# cnc-diff-line-driver.net
KiCad netlist of a schematic drawn in EAGLE
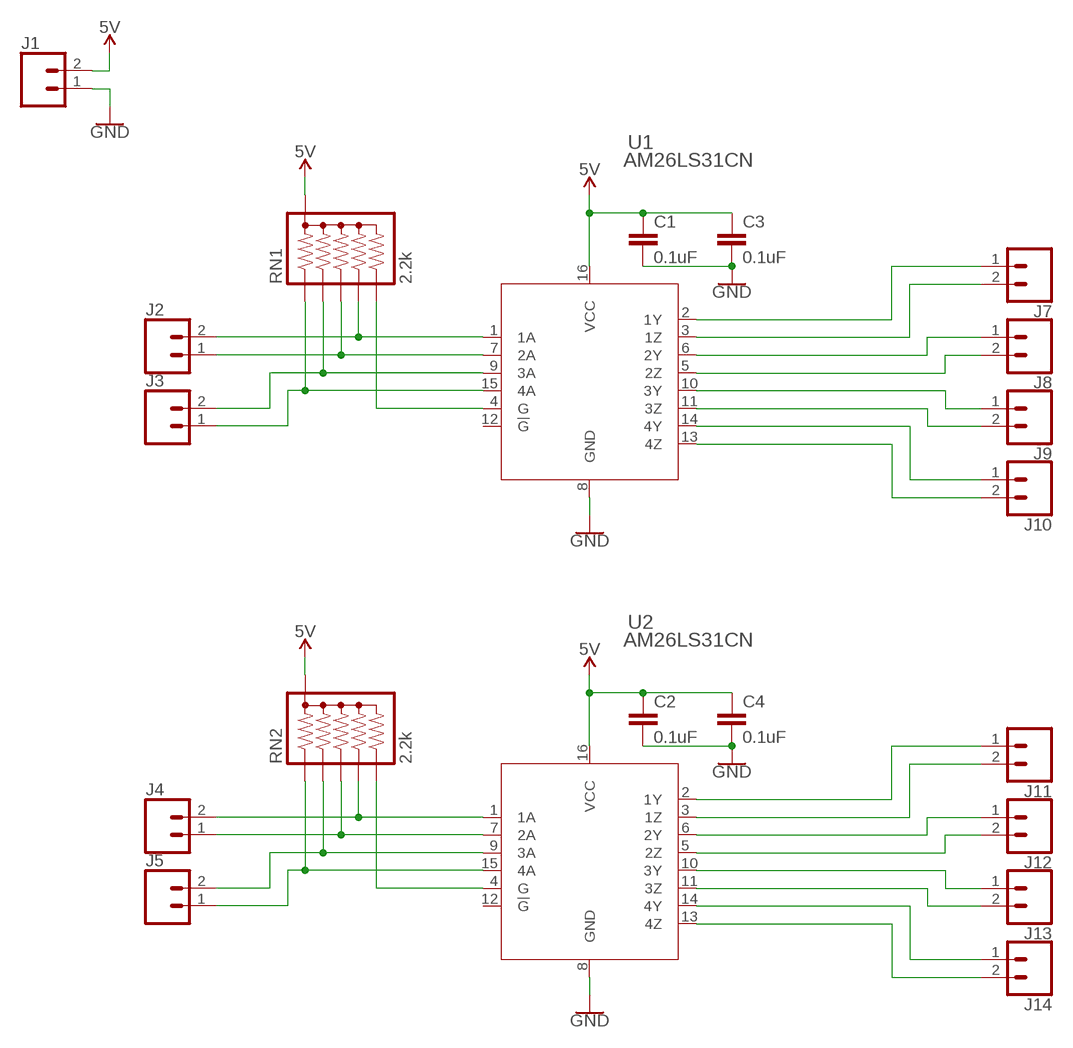
[diagram p0: schematic, sheet 1]

(export (version "E")
  (design (tool "Eeschema 10.0.6"))
  (components
    (comp (ref "C1")
      (value "0.1uF")
      (footprint "eagle-import:CAP-PTH-SMALL-KIT")
      (libsource (lib "eagle-import") (part "0.1UF-KIT-EZ-50V-20%"))
    )
    (comp (ref "C2")
      (value "0.1uF")
      (footprint "eagle-import:CAP-PTH-SMALL-KIT")
      (libsource (lib "eagle-import") (part "0.1UF-KIT-EZ-50V-20%"))
    )
    (comp (ref "C3")
      (value "0.1uF")
      (footprint "eagle-import:CAP-PTH-SMALL-KIT")
      (libsource (lib "eagle-import") (part "0.1UF-KIT-EZ-50V-20%"))
    )
    (comp (ref "C4")
      (value "0.1uF")
      (footprint "eagle-import:CAP-PTH-SMALL-KIT")
      (libsource (lib "eagle-import") (part "0.1UF-KIT-EZ-50V-20%"))
    )
    (comp (ref "J1")
      (value "PHOENIX_CON_5.08MM_SCREW_1888687")
      (footprint "eagle-import:SCREWTERMINAL-5MM-2")
      (libsource (lib "eagle-import") (part "PHOENIX_CON_5.08MM_SCREW_1888687"))
    )
    (comp (ref "J2")
      (value "PHOENIX_CON_5.08MM_SCREW_1888687")
      (footprint "eagle-import:SCREWTERMINAL-5MM-2")
      (libsource (lib "eagle-import") (part "PHOENIX_CON_5.08MM_SCREW_1888687"))
    )
    (comp (ref "J3")
      (value "PHOENIX_CON_5.08MM_SCREW_1888687")
      (footprint "eagle-import:SCREWTERMINAL-5MM-2")
      (libsource (lib "eagle-import") (part "PHOENIX_CON_5.08MM_SCREW_1888687"))
    )
    (comp (ref "J4")
      (value "PHOENIX_CON_5.08MM_SCREW_1888687")
      (footprint "eagle-import:SCREWTERMINAL-5MM-2")
      (libsource (lib "eagle-import") (part "PHOENIX_CON_5.08MM_SCREW_1888687"))
    )
    (comp (ref "J5")
      (value "PHOENIX_CON_5.08MM_SCREW_1888687")
      (footprint "eagle-import:SCREWTERMINAL-5MM-2")
      (libsource (lib "eagle-import") (part "PHOENIX_CON_5.08MM_SCREW_1888687"))
    )
    (comp (ref "J7")
      (value "PHOENIX_CON_5.08MM_SCREW_1888687")
      (footprint "eagle-import:SCREWTERMINAL-5MM-2")
      (libsource (lib "eagle-import") (part "PHOENIX_CON_5.08MM_SCREW_1888687"))
    )
    (comp (ref "J8")
      (value "PHOENIX_CON_5.08MM_SCREW_1888687")
      (footprint "eagle-import:SCREWTERMINAL-5MM-2")
      (libsource (lib "eagle-import") (part "PHOENIX_CON_5.08MM_SCREW_1888687"))
    )
    (comp (ref "J9")
      (value "PHOENIX_CON_5.08MM_SCREW_1888687")
      (footprint "eagle-import:SCREWTERMINAL-5MM-2")
      (libsource (lib "eagle-import") (part "PHOENIX_CON_5.08MM_SCREW_1888687"))
    )
    (comp (ref "J10")
      (value "PHOENIX_CON_5.08MM_SCREW_1888687")
      (footprint "eagle-import:SCREWTERMINAL-5MM-2")
      (libsource (lib "eagle-import") (part "PHOENIX_CON_5.08MM_SCREW_1888687"))
    )
    (comp (ref "J11")
      (value "PHOENIX_CON_5.08MM_SCREW_1888687")
      (footprint "eagle-import:SCREWTERMINAL-5MM-2")
      (libsource (lib "eagle-import") (part "PHOENIX_CON_5.08MM_SCREW_1888687"))
    )
    (comp (ref "J12")
      (value "PHOENIX_CON_5.08MM_SCREW_1888687")
      (footprint "eagle-import:SCREWTERMINAL-5MM-2")
      (libsource (lib "eagle-import") (part "PHOENIX_CON_5.08MM_SCREW_1888687"))
    )
    (comp (ref "J13")
      (value "PHOENIX_CON_5.08MM_SCREW_1888687")
      (footprint "eagle-import:SCREWTERMINAL-5MM-2")
      (libsource (lib "eagle-import") (part "PHOENIX_CON_5.08MM_SCREW_1888687"))
    )
    (comp (ref "J14")
      (value "PHOENIX_CON_5.08MM_SCREW_1888687")
      (footprint "eagle-import:SCREWTERMINAL-5MM-2")
      (libsource (lib "eagle-import") (part "PHOENIX_CON_5.08MM_SCREW_1888687"))
    )
    (comp (ref "RN1")
      (value "2.2k")
      (footprint "eagle-import:RPACK-SIP-PTH-5")
      (libsource (lib "eagle-import") (part "10K_BUSSED_5"))
    )
    (comp (ref "RN2")
      (value "2.2k")
      (footprint "eagle-import:RPACK-SIP-PTH-5")
      (libsource (lib "eagle-import") (part "10K_BUSSED_5"))
    )
    (comp (ref "U1")
      (value "AM26LS31CN")
      (footprint "eagle-import:N16")
      (libsource (lib "eagle-import") (part "AM26LS31CN"))
    )
    (comp (ref "U2")
      (value "AM26LS31CN")
      (footprint "eagle-import:N16")
      (libsource (lib "eagle-import") (part "AM26LS31CN"))
    )
  )
  (nets
    (net (code "1") (name "5V") (class "Default")
      (node (ref "C1") (pin "1") (pinfunction "1_1") (pintype "passive"))
      (node (ref "C2") (pin "1") (pinfunction "1_1") (pintype "passive"))
      (node (ref "C3") (pin "1") (pinfunction "1_1") (pintype "passive"))
      (node (ref "C4") (pin "1") (pinfunction "1_1") (pintype "passive"))
      (node (ref "J1") (pin "2") (pinfunction "2_2") (pintype "passive"))
      (node (ref "RN1") (pin "P$1") (pinfunction "1_P$1") (pintype "passive"))
      (node (ref "RN2") (pin "P$1") (pinfunction "1_P$1") (pintype "passive"))
      (node (ref "U1") (pin "16") (pinfunction "VCC_16") (pintype "power_in"))
      (node (ref "U2") (pin "16") (pinfunction "VCC_16") (pintype "power_in"))
    )
    (net (code "2") (name "GND") (class "Default")
      (node (ref "C1") (pin "2") (pinfunction "2_2") (pintype "passive"))
      (node (ref "C2") (pin "2") (pinfunction "2_2") (pintype "passive"))
      (node (ref "C3") (pin "2") (pinfunction "2_2") (pintype "passive"))
      (node (ref "C4") (pin "2") (pinfunction "2_2") (pintype "passive"))
      (node (ref "J1") (pin "1") (pinfunction "1_1") (pintype "passive"))
      (node (ref "U1") (pin "8") (pinfunction "GND_8") (pintype "power_in"))
      (node (ref "U2") (pin "8") (pinfunction "GND_8") (pintype "power_in"))
    )
    (net (code "3") (name "Net-(RN1-2)") (class "Default")
      (node (ref "J3") (pin "1") (pinfunction "1_1") (pintype "passive"))
      (node (ref "RN1") (pin "P$2") (pinfunction "2_P$2") (pintype "passive"))
      (node (ref "U1") (pin "15") (pinfunction "4A_15") (pintype "input"))
    )
    (net (code "4") (name "Net-(RN1-3)") (class "Default")
      (node (ref "J3") (pin "2") (pinfunction "2_2") (pintype "passive"))
      (node (ref "RN1") (pin "P$3") (pinfunction "3_P$3") (pintype "passive"))
      (node (ref "U1") (pin "9") (pinfunction "3A_9") (pintype "input"))
    )
    (net (code "5") (name "Net-(RN1-4)") (class "Default")
      (node (ref "J2") (pin "1") (pinfunction "1_1") (pintype "passive"))
      (node (ref "RN1") (pin "P$4") (pinfunction "4_P$4") (pintype "passive"))
      (node (ref "U1") (pin "7") (pinfunction "2A_7") (pintype "input"))
    )
    (net (code "6") (name "Net-(RN1-5)") (class "Default")
      (node (ref "J2") (pin "2") (pinfunction "2_2") (pintype "passive"))
      (node (ref "RN1") (pin "P$5") (pinfunction "5_P$5") (pintype "passive"))
      (node (ref "U1") (pin "1") (pinfunction "1A_1") (pintype "input"))
    )
    (net (code "7") (name "Net-(RN1-6)") (class "Default")
      (node (ref "RN1") (pin "P$6") (pinfunction "6_P$6") (pintype "passive"))
      (node (ref "U1") (pin "4") (pinfunction "G_4") (pintype "bidirectional"))
    )
    (net (code "8") (name "Net-(RN2-2)") (class "Default")
      (node (ref "J5") (pin "1") (pinfunction "1_1") (pintype "passive"))
      (node (ref "RN2") (pin "P$2") (pinfunction "2_P$2") (pintype "passive"))
      (node (ref "U2") (pin "15") (pinfunction "4A_15") (pintype "input"))
    )
    (net (code "9") (name "Net-(RN2-3)") (class "Default")
      (node (ref "J5") (pin "2") (pinfunction "2_2") (pintype "passive"))
      (node (ref "RN2") (pin "P$3") (pinfunction "3_P$3") (pintype "passive"))
      (node (ref "U2") (pin "9") (pinfunction "3A_9") (pintype "input"))
    )
    (net (code "10") (name "Net-(RN2-4)") (class "Default")
      (node (ref "J4") (pin "1") (pinfunction "1_1") (pintype "passive"))
      (node (ref "RN2") (pin "P$4") (pinfunction "4_P$4") (pintype "passive"))
      (node (ref "U2") (pin "7") (pinfunction "2A_7") (pintype "input"))
    )
    (net (code "11") (name "Net-(RN2-5)") (class "Default")
      (node (ref "J4") (pin "2") (pinfunction "2_2") (pintype "passive"))
      (node (ref "RN2") (pin "P$5") (pinfunction "5_P$5") (pintype "passive"))
      (node (ref "U2") (pin "1") (pinfunction "1A_1") (pintype "input"))
    )
    (net (code "12") (name "Net-(RN2-6)") (class "Default")
      (node (ref "RN2") (pin "P$6") (pinfunction "6_P$6") (pintype "passive"))
      (node (ref "U2") (pin "4") (pinfunction "G_4") (pintype "bidirectional"))
    )
    (net (code "13") (name "Net-(U1-1Y)") (class "Default")
      (node (ref "J7") (pin "1") (pinfunction "1_1") (pintype "passive"))
      (node (ref "U1") (pin "2") (pinfunction "1Y_2") (pintype "output"))
    )
    (net (code "14") (name "Net-(U1-1Z)") (class "Default")
      (node (ref "J7") (pin "2") (pinfunction "2_2") (pintype "passive"))
      (node (ref "U1") (pin "3") (pinfunction "1Z_3") (pintype "output"))
    )
    (net (code "15") (name "Net-(U1-2Y)") (class "Default")
      (node (ref "J8") (pin "1") (pinfunction "1_1") (pintype "passive"))
      (node (ref "U1") (pin "6") (pinfunction "2Y_6") (pintype "output"))
    )
    (net (code "16") (name "Net-(U1-2Z)") (class "Default")
      (node (ref "J8") (pin "2") (pinfunction "2_2") (pintype "passive"))
      (node (ref "U1") (pin "5") (pinfunction "2Z_5") (pintype "output"))
    )
    (net (code "17") (name "Net-(U1-3Y)") (class "Default")
      (node (ref "J9") (pin "1") (pinfunction "1_1") (pintype "passive"))
      (node (ref "U1") (pin "10") (pinfunction "3Y_10") (pintype "output"))
    )
    (net (code "18") (name "Net-(U1-3Z)") (class "Default")
      (node (ref "J9") (pin "2") (pinfunction "2_2") (pintype "passive"))
      (node (ref "U1") (pin "11") (pinfunction "3Z_11") (pintype "output"))
    )
    (net (code "19") (name "Net-(U1-4Y)") (class "Default")
      (node (ref "J10") (pin "1") (pinfunction "1_1") (pintype "passive"))
      (node (ref "U1") (pin "14") (pinfunction "4Y_14") (pintype "output"))
    )
    (net (code "20") (name "Net-(U1-4Z)") (class "Default")
      (node (ref "J10") (pin "2") (pinfunction "2_2") (pintype "passive"))
      (node (ref "U1") (pin "13") (pinfunction "4Z_13") (pintype "output"))
    )
    (net (code "21") (name "Net-(U2-1Y)") (class "Default")
      (node (ref "J11") (pin "1") (pinfunction "1_1") (pintype "passive"))
      (node (ref "U2") (pin "2") (pinfunction "1Y_2") (pintype "output"))
    )
    (net (code "22") (name "Net-(U2-1Z)") (class "Default")
      (node (ref "J11") (pin "2") (pinfunction "2_2") (pintype "passive"))
      (node (ref "U2") (pin "3") (pinfunction "1Z_3") (pintype "output"))
    )
    (net (code "23") (name "Net-(U2-2Y)") (class "Default")
      (node (ref "J12") (pin "1") (pinfunction "1_1") (pintype "passive"))
      (node (ref "U2") (pin "6") (pinfunction "2Y_6") (pintype "output"))
    )
    (net (code "24") (name "Net-(U2-2Z)") (class "Default")
      (node (ref "J12") (pin "2") (pinfunction "2_2") (pintype "passive"))
      (node (ref "U2") (pin "5") (pinfunction "2Z_5") (pintype "output"))
    )
    (net (code "25") (name "Net-(U2-3Y)") (class "Default")
      (node (ref "J13") (pin "1") (pinfunction "1_1") (pintype "passive"))
      (node (ref "U2") (pin "10") (pinfunction "3Y_10") (pintype "output"))
    )
    (net (code "26") (name "Net-(U2-3Z)") (class "Default")
      (node (ref "J13") (pin "2") (pinfunction "2_2") (pintype "passive"))
      (node (ref "U2") (pin "11") (pinfunction "3Z_11") (pintype "output"))
    )
    (net (code "27") (name "Net-(U2-4Y)") (class "Default")
      (node (ref "J14") (pin "1") (pinfunction "1_1") (pintype "passive"))
      (node (ref "U2") (pin "14") (pinfunction "4Y_14") (pintype "output"))
    )
    (net (code "28") (name "Net-(U2-4Z)") (class "Default")
      (node (ref "J14") (pin "2") (pinfunction "2_2") (pintype "passive"))
      (node (ref "U2") (pin "13") (pinfunction "4Z_13") (pintype "output"))
    )
    (net (code "29") (name "unconnected-(U1-~{G}-Pad12)") (class "Default")
      (node (ref "U1") (pin "12") (pinfunction "~{G}_12") (pintype "bidirectional"))
    )
    (net (code "30") (name "unconnected-(U2-~{G}-Pad12)") (class "Default")
      (node (ref "U2") (pin "12") (pinfunction "~{G}_12") (pintype "bidirectional"))
    )
  )
)
